# 180_schematic_3_layer.net
KiCad netlist of a schematic drawn in EAGLE
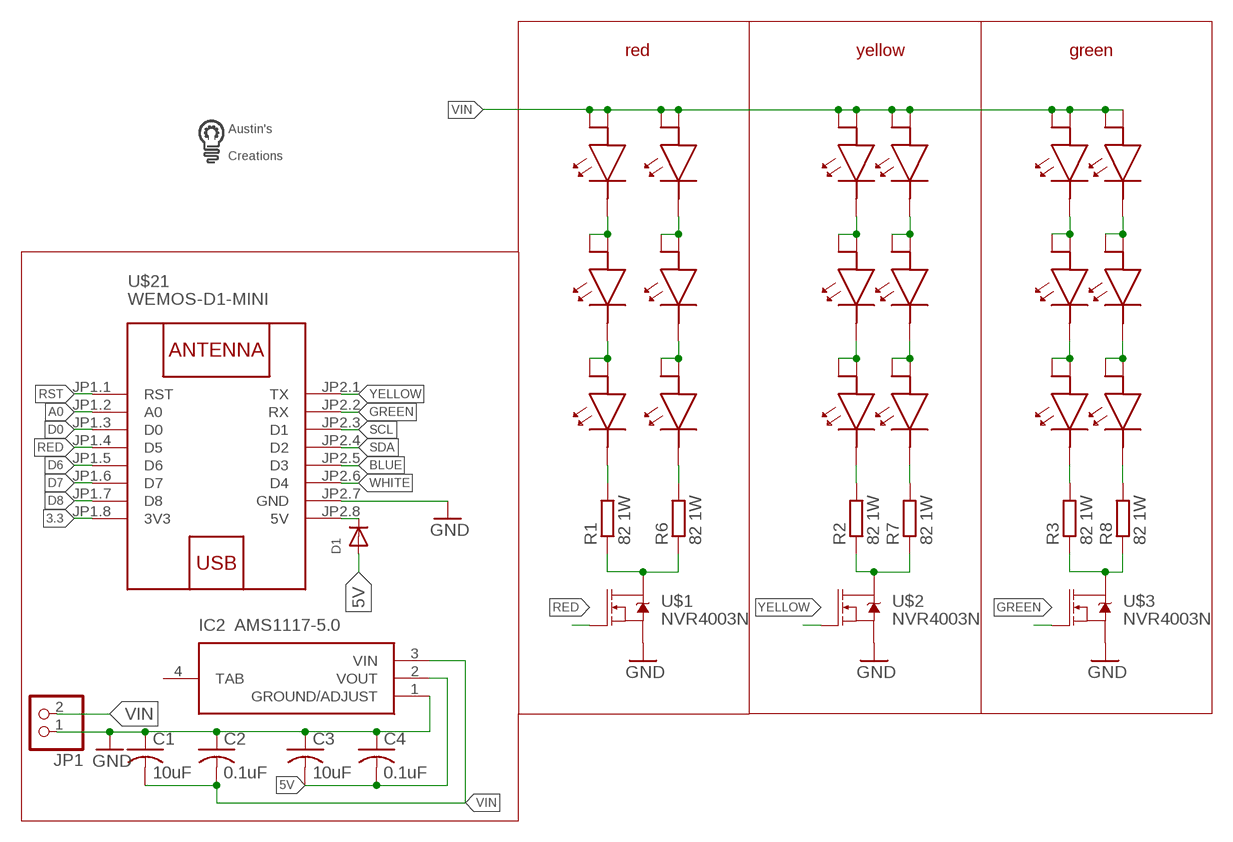
[diagram p0: schematic, sheet 1]

(export (version "E")
  (design (tool "Eeschema 10.0.6"))
  (components
    (comp (ref "C1")
      (value "10uF")
      (footprint "eagle-import:C0603")
      (libsource (lib "eagle-import") (part "C-USC0603"))
    )
    (comp (ref "C2")
      (value "0.1uF")
      (footprint "eagle-import:C0603")
      (libsource (lib "eagle-import") (part "C-USC0603"))
    )
    (comp (ref "C3")
      (value "10uF")
      (footprint "eagle-import:C0603")
      (libsource (lib "eagle-import") (part "C-USC0603"))
    )
    (comp (ref "C4")
      (value "0.1uF")
      (footprint "eagle-import:C0603")
      (libsource (lib "eagle-import") (part "C-USC0603"))
    )
    (comp (ref "D1")
      (value "DIODESOD-123")
      (footprint "eagle-import:SOD-123")
      (libsource (lib "eagle-import") (part "DIODESOD-123"))
    )
    (comp (ref "IC2")
      (value "AMS1117-5.0")
      (footprint "eagle-import:SOT229P700X180-4N")
      (libsource (lib "eagle-import") (part "AMS1117-5.0"))
    )
    (comp (ref "JP1")
      (value "PINHD-1X2")
      (footprint "eagle-import:1X02")
      (libsource (lib "eagle-import") (part "PINHD-1X2"))
    )
    (comp (ref "R1")
      (value "82 1W")
      (footprint "eagle-import:R2010")
      (libsource (lib "eagle-import") (part "R-EU_R2010"))
    )
    (comp (ref "R2")
      (value "82 1W")
      (footprint "eagle-import:R2010")
      (libsource (lib "eagle-import") (part "R-EU_R2010"))
    )
    (comp (ref "R3")
      (value "82 1W")
      (footprint "eagle-import:R2010")
      (libsource (lib "eagle-import") (part "R-EU_R2010"))
    )
    (comp (ref "R6")
      (value "82 1W")
      (footprint "eagle-import:R2010")
      (libsource (lib "eagle-import") (part "R-EU_R2010"))
    )
    (comp (ref "R7")
      (value "82 1W")
      (footprint "eagle-import:R2010")
      (libsource (lib "eagle-import") (part "R-EU_R2010"))
    )
    (comp (ref "R8")
      (value "82 1W")
      (footprint "eagle-import:R2010")
      (libsource (lib "eagle-import") (part "R-EU_R2010"))
    )
    (comp (ref "U$1")
      (value "NVR4003N")
      (footprint "eagle-import:SOT23")
      (libsource (lib "eagle-import") (part "NVR4003N"))
    )
    (comp (ref "U$2")
      (value "NVR4003N")
      (footprint "eagle-import:SOT23")
      (libsource (lib "eagle-import") (part "NVR4003N"))
    )
    (comp (ref "U$3")
      (value "NVR4003N")
      (footprint "eagle-import:SOT23")
      (libsource (lib "eagle-import") (part "NVR4003N"))
    )
    (comp (ref "U$6")
      (value "5730LED")
      (footprint "eagle-import:5730LED")
      (libsource (lib "eagle-import") (part "5730LED"))
    )
    (comp (ref "U$7")
      (value "5730LED")
      (footprint "eagle-import:5730LED")
      (libsource (lib "eagle-import") (part "5730LED"))
    )
    (comp (ref "U$8")
      (value "5730LED")
      (footprint "eagle-import:5730LED")
      (libsource (lib "eagle-import") (part "5730LED"))
    )
    (comp (ref "U$9")
      (value "5730LED")
      (footprint "eagle-import:5730LED")
      (libsource (lib "eagle-import") (part "5730LED"))
    )
    (comp (ref "U$10")
      (value "5730LED")
      (footprint "eagle-import:5730LED")
      (libsource (lib "eagle-import") (part "5730LED"))
    )
    (comp (ref "U$11")
      (value "5730LED")
      (footprint "eagle-import:5730LED")
      (libsource (lib "eagle-import") (part "5730LED"))
    )
    (comp (ref "U$12")
      (value "5730LED")
      (footprint "eagle-import:5730LED")
      (libsource (lib "eagle-import") (part "5730LED"))
    )
    (comp (ref "U$13")
      (value "5730LED")
      (footprint "eagle-import:5730LED")
      (libsource (lib "eagle-import") (part "5730LED"))
    )
    (comp (ref "U$14")
      (value "5730LED")
      (footprint "eagle-import:5730LED")
      (libsource (lib "eagle-import") (part "5730LED"))
    )
    (comp (ref "U$21")
      (value "WEMOS-D1-MINI")
      (footprint "eagle-import:WEMOS-D1-MINI")
      (libsource (lib "eagle-import") (part "WEMOS-D1-MINI"))
    )
    (comp (ref "U$22")
      (value "LOGO")
      (footprint "eagle-import:LOGO")
      (libsource (lib "eagle-import") (part "LOGO"))
    )
    (comp (ref "U$23")
      (value "5730LED")
      (footprint "eagle-import:5730LED")
      (libsource (lib "eagle-import") (part "5730LED"))
    )
    (comp (ref "U$24")
      (value "5730LED")
      (footprint "eagle-import:5730LED")
      (libsource (lib "eagle-import") (part "5730LED"))
    )
    (comp (ref "U$25")
      (value "5730LED")
      (footprint "eagle-import:5730LED")
      (libsource (lib "eagle-import") (part "5730LED"))
    )
    (comp (ref "U$26")
      (value "5730LED")
      (footprint "eagle-import:5730LED")
      (libsource (lib "eagle-import") (part "5730LED"))
    )
    (comp (ref "U$27")
      (value "5730LED")
      (footprint "eagle-import:5730LED")
      (libsource (lib "eagle-import") (part "5730LED"))
    )
    (comp (ref "U$28")
      (value "5730LED")
      (footprint "eagle-import:5730LED")
      (libsource (lib "eagle-import") (part "5730LED"))
    )
    (comp (ref "U$29")
      (value "5730LED")
      (footprint "eagle-import:5730LED")
      (libsource (lib "eagle-import") (part "5730LED"))
    )
    (comp (ref "U$30")
      (value "5730LED")
      (footprint "eagle-import:5730LED")
      (libsource (lib "eagle-import") (part "5730LED"))
    )
    (comp (ref "U$31")
      (value "5730LED")
      (footprint "eagle-import:5730LED")
      (libsource (lib "eagle-import") (part "5730LED"))
    )
  )
  (nets
    (net (code "1") (name "3.3") (class "Default")
      (node (ref "U$21") (pin "JP1.8") (pinfunction "3V3_JP1.8") (pintype "power_in"))
    )
    (net (code "2") (name "5V") (class "Default")
      (node (ref "C3") (pin "2") (pinfunction "2_2") (pintype "passive"))
      (node (ref "C4") (pin "2") (pinfunction "2_2") (pintype "passive"))
      (node (ref "D1") (pin "A") (pinfunction "A_A") (pintype "passive"))
      (node (ref "IC2") (pin "2") (pinfunction "VOUT_2") (pintype "bidirectional"))
    )
    (net (code "3") (name "A0") (class "Default")
      (node (ref "U$21") (pin "JP1.2") (pinfunction "A0_JP1.2") (pintype "bidirectional"))
    )
    (net (code "4") (name "BLUE") (class "Default")
      (node (ref "U$21") (pin "JP2.5") (pinfunction "D3_JP2.5") (pintype "bidirectional"))
    )
    (net (code "5") (name "D0") (class "Default")
      (node (ref "U$21") (pin "JP1.3") (pinfunction "D0_JP1.3") (pintype "bidirectional"))
    )
    (net (code "6") (name "D6") (class "Default")
      (node (ref "U$21") (pin "JP1.5") (pinfunction "D6_JP1.5") (pintype "bidirectional"))
    )
    (net (code "7") (name "D7") (class "Default")
      (node (ref "U$21") (pin "JP1.6") (pinfunction "D7_JP1.6") (pintype "bidirectional"))
    )
    (net (code "8") (name "D8") (class "Default")
      (node (ref "U$21") (pin "JP1.7") (pinfunction "D8_JP1.7") (pintype "bidirectional"))
    )
    (net (code "9") (name "GND") (class "Default")
      (node (ref "C1") (pin "1") (pinfunction "1_1") (pintype "passive"))
      (node (ref "C2") (pin "1") (pinfunction "1_1") (pintype "passive"))
      (node (ref "C3") (pin "1") (pinfunction "1_1") (pintype "passive"))
      (node (ref "C4") (pin "1") (pinfunction "1_1") (pintype "passive"))
      (node (ref "IC2") (pin "1") (pinfunction "GROUND/ADJUST_1") (pintype "bidirectional"))
      (node (ref "JP1") (pin "1") (pinfunction "1_1") (pintype "passive"))
      (node (ref "U$1") (pin "3") (pinfunction "S_3") (pintype "bidirectional"))
      (node (ref "U$2") (pin "3") (pinfunction "S_3") (pintype "bidirectional"))
      (node (ref "U$21") (pin "JP2.7") (pinfunction "GND_JP2.7") (pintype "power_in"))
      (node (ref "U$3") (pin "3") (pinfunction "S_3") (pintype "bidirectional"))
    )
    (net (code "10") (name "GREEN") (class "Default")
      (node (ref "U$21") (pin "JP2.2") (pinfunction "RX_JP2.2") (pintype "bidirectional"))
      (node (ref "U$3") (pin "2") (pinfunction "G_2") (pintype "bidirectional"))
    )
    (net (code "11") (name "Net-(R1-Pad2)") (class "Default")
      (node (ref "R1") (pin "2") (pinfunction "2_2") (pintype "passive"))
      (node (ref "U$8") (pin "P$2") (pinfunction "P$2_P$2") (pintype "bidirectional"))
    )
    (net (code "12") (name "Net-(R2-Pad2)") (class "Default")
      (node (ref "R2") (pin "2") (pinfunction "2_2") (pintype "passive"))
      (node (ref "U$11") (pin "P$2") (pinfunction "P$2_P$2") (pintype "bidirectional"))
    )
    (net (code "13") (name "Net-(R3-Pad2)") (class "Default")
      (node (ref "R3") (pin "2") (pinfunction "2_2") (pintype "passive"))
      (node (ref "U$14") (pin "P$2") (pinfunction "P$2_P$2") (pintype "bidirectional"))
    )
    (net (code "14") (name "Net-(R6-Pad2)") (class "Default")
      (node (ref "R6") (pin "2") (pinfunction "2_2") (pintype "passive"))
      (node (ref "U$25") (pin "P$2") (pinfunction "P$2_P$2") (pintype "bidirectional"))
    )
    (net (code "15") (name "Net-(R7-Pad2)") (class "Default")
      (node (ref "R7") (pin "2") (pinfunction "2_2") (pintype "passive"))
      (node (ref "U$28") (pin "P$2") (pinfunction "P$2_P$2") (pintype "bidirectional"))
    )
    (net (code "16") (name "Net-(R8-Pad2)") (class "Default")
      (node (ref "R8") (pin "2") (pinfunction "2_2") (pintype "passive"))
      (node (ref "U$31") (pin "P$2") (pinfunction "P$2_P$2") (pintype "bidirectional"))
    )
    (net (code "17") (name "Net-(U$1-D)") (class "Default")
      (node (ref "R1") (pin "1") (pinfunction "1_1") (pintype "passive"))
      (node (ref "R6") (pin "1") (pinfunction "1_1") (pintype "passive"))
      (node (ref "U$1") (pin "1") (pinfunction "D_1") (pintype "bidirectional"))
    )
    (net (code "18") (name "Net-(U$2-D)") (class "Default")
      (node (ref "R2") (pin "1") (pinfunction "1_1") (pintype "passive"))
      (node (ref "R7") (pin "1") (pinfunction "1_1") (pintype "passive"))
      (node (ref "U$2") (pin "1") (pinfunction "D_1") (pintype "bidirectional"))
    )
    (net (code "19") (name "Net-(U$3-D)") (class "Default")
      (node (ref "R3") (pin "1") (pinfunction "1_1") (pintype "passive"))
      (node (ref "R8") (pin "1") (pinfunction "1_1") (pintype "passive"))
      (node (ref "U$3") (pin "1") (pinfunction "D_1") (pintype "bidirectional"))
    )
    (net (code "20") (name "Net-(U$6-PadP$2)") (class "Default")
      (node (ref "U$6") (pin "P$2") (pinfunction "P$2_P$2") (pintype "bidirectional"))
      (node (ref "U$7") (pin "P$1") (pinfunction "P$1_P$1") (pintype "bidirectional"))
      (node (ref "U$7") (pin "P$3") (pinfunction "P$3_P$3") (pintype "bidirectional"))
    )
    (net (code "21") (name "Net-(U$7-PadP$2)") (class "Default")
      (node (ref "U$7") (pin "P$2") (pinfunction "P$2_P$2") (pintype "bidirectional"))
      (node (ref "U$8") (pin "P$1") (pinfunction "P$1_P$1") (pintype "bidirectional"))
      (node (ref "U$8") (pin "P$3") (pinfunction "P$3_P$3") (pintype "bidirectional"))
    )
    (net (code "22") (name "Net-(U$10-PadP$1)") (class "Default")
      (node (ref "U$10") (pin "P$1") (pinfunction "P$1_P$1") (pintype "bidirectional"))
      (node (ref "U$10") (pin "P$3") (pinfunction "P$3_P$3") (pintype "bidirectional"))
      (node (ref "U$9") (pin "P$2") (pinfunction "P$2_P$2") (pintype "bidirectional"))
    )
    (net (code "23") (name "Net-(U$10-PadP$2)") (class "Default")
      (node (ref "U$10") (pin "P$2") (pinfunction "P$2_P$2") (pintype "bidirectional"))
      (node (ref "U$11") (pin "P$1") (pinfunction "P$1_P$1") (pintype "bidirectional"))
      (node (ref "U$11") (pin "P$3") (pinfunction "P$3_P$3") (pintype "bidirectional"))
    )
    (net (code "24") (name "Net-(U$12-PadP$2)") (class "Default")
      (node (ref "U$12") (pin "P$2") (pinfunction "P$2_P$2") (pintype "bidirectional"))
      (node (ref "U$13") (pin "P$1") (pinfunction "P$1_P$1") (pintype "bidirectional"))
      (node (ref "U$13") (pin "P$3") (pinfunction "P$3_P$3") (pintype "bidirectional"))
    )
    (net (code "25") (name "Net-(U$13-PadP$2)") (class "Default")
      (node (ref "U$13") (pin "P$2") (pinfunction "P$2_P$2") (pintype "bidirectional"))
      (node (ref "U$14") (pin "P$1") (pinfunction "P$1_P$1") (pintype "bidirectional"))
      (node (ref "U$14") (pin "P$3") (pinfunction "P$3_P$3") (pintype "bidirectional"))
    )
    (net (code "26") (name "Net-(U$21-5V)") (class "Default")
      (node (ref "D1") (pin "C") (pinfunction "C_C") (pintype "passive"))
      (node (ref "U$21") (pin "JP2.8") (pinfunction "5V_JP2.8") (pintype "power_in"))
    )
    (net (code "27") (name "Net-(U$23-PadP$2)") (class "Default")
      (node (ref "U$23") (pin "P$2") (pinfunction "P$2_P$2") (pintype "bidirectional"))
      (node (ref "U$24") (pin "P$1") (pinfunction "P$1_P$1") (pintype "bidirectional"))
      (node (ref "U$24") (pin "P$3") (pinfunction "P$3_P$3") (pintype "bidirectional"))
    )
    (net (code "28") (name "Net-(U$24-PadP$2)") (class "Default")
      (node (ref "U$24") (pin "P$2") (pinfunction "P$2_P$2") (pintype "bidirectional"))
      (node (ref "U$25") (pin "P$1") (pinfunction "P$1_P$1") (pintype "bidirectional"))
      (node (ref "U$25") (pin "P$3") (pinfunction "P$3_P$3") (pintype "bidirectional"))
    )
    (net (code "29") (name "Net-(U$26-PadP$2)") (class "Default")
      (node (ref "U$26") (pin "P$2") (pinfunction "P$2_P$2") (pintype "bidirectional"))
      (node (ref "U$27") (pin "P$1") (pinfunction "P$1_P$1") (pintype "bidirectional"))
      (node (ref "U$27") (pin "P$3") (pinfunction "P$3_P$3") (pintype "bidirectional"))
    )
    (net (code "30") (name "Net-(U$27-PadP$2)") (class "Default")
      (node (ref "U$27") (pin "P$2") (pinfunction "P$2_P$2") (pintype "bidirectional"))
      (node (ref "U$28") (pin "P$1") (pinfunction "P$1_P$1") (pintype "bidirectional"))
      (node (ref "U$28") (pin "P$3") (pinfunction "P$3_P$3") (pintype "bidirectional"))
    )
    (net (code "31") (name "Net-(U$29-PadP$2)") (class "Default")
      (node (ref "U$29") (pin "P$2") (pinfunction "P$2_P$2") (pintype "bidirectional"))
      (node (ref "U$30") (pin "P$1") (pinfunction "P$1_P$1") (pintype "bidirectional"))
      (node (ref "U$30") (pin "P$3") (pinfunction "P$3_P$3") (pintype "bidirectional"))
    )
    (net (code "32") (name "Net-(U$30-PadP$2)") (class "Default")
      (node (ref "U$30") (pin "P$2") (pinfunction "P$2_P$2") (pintype "bidirectional"))
      (node (ref "U$31") (pin "P$1") (pinfunction "P$1_P$1") (pintype "bidirectional"))
      (node (ref "U$31") (pin "P$3") (pinfunction "P$3_P$3") (pintype "bidirectional"))
    )
    (net (code "33") (name "RED") (class "Default")
      (node (ref "U$1") (pin "2") (pinfunction "G_2") (pintype "bidirectional"))
      (node (ref "U$21") (pin "JP1.4") (pinfunction "D5_JP1.4") (pintype "bidirectional"))
    )
    (net (code "34") (name "RST") (class "Default")
      (node (ref "U$21") (pin "JP1.1") (pinfunction "RST_JP1.1") (pintype "bidirectional"))
    )
    (net (code "35") (name "SCL") (class "Default")
      (node (ref "U$21") (pin "JP2.3") (pinfunction "D1_JP2.3") (pintype "bidirectional"))
    )
    (net (code "36") (name "SDA") (class "Default")
      (node (ref "U$21") (pin "JP2.4") (pinfunction "D2_JP2.4") (pintype "bidirectional"))
    )
    (net (code "37") (name "VIN") (class "Default")
      (node (ref "C1") (pin "2") (pinfunction "2_2") (pintype "passive"))
      (node (ref "C2") (pin "2") (pinfunction "2_2") (pintype "passive"))
      (node (ref "IC2") (pin "3") (pinfunction "VIN_3") (pintype "bidirectional"))
      (node (ref "JP1") (pin "2") (pinfunction "2_2") (pintype "passive"))
      (node (ref "U$12") (pin "P$1") (pinfunction "P$1_P$1") (pintype "bidirectional"))
      (node (ref "U$12") (pin "P$3") (pinfunction "P$3_P$3") (pintype "bidirectional"))
      (node (ref "U$23") (pin "P$1") (pinfunction "P$1_P$1") (pintype "bidirectional"))
      (node (ref "U$23") (pin "P$3") (pinfunction "P$3_P$3") (pintype "bidirectional"))
      (node (ref "U$26") (pin "P$1") (pinfunction "P$1_P$1") (pintype "bidirectional"))
      (node (ref "U$26") (pin "P$3") (pinfunction "P$3_P$3") (pintype "bidirectional"))
      (node (ref "U$29") (pin "P$1") (pinfunction "P$1_P$1") (pintype "bidirectional"))
      (node (ref "U$29") (pin "P$3") (pinfunction "P$3_P$3") (pintype "bidirectional"))
      (node (ref "U$6") (pin "P$1") (pinfunction "P$1_P$1") (pintype "bidirectional"))
      (node (ref "U$6") (pin "P$3") (pinfunction "P$3_P$3") (pintype "bidirectional"))
      (node (ref "U$9") (pin "P$1") (pinfunction "P$1_P$1") (pintype "bidirectional"))
      (node (ref "U$9") (pin "P$3") (pinfunction "P$3_P$3") (pintype "bidirectional"))
    )
    (net (code "38") (name "WHITE") (class "Default")
      (node (ref "U$21") (pin "JP2.6") (pinfunction "D4_JP2.6") (pintype "bidirectional"))
    )
    (net (code "39") (name "YELLOW") (class "Default")
      (node (ref "U$2") (pin "2") (pinfunction "G_2") (pintype "bidirectional"))
      (node (ref "U$21") (pin "JP2.1") (pinfunction "TX_JP2.1") (pintype "bidirectional"))
    )
    (net (code "40") (name "unconnected-(IC2-TAB-Pad4)") (class "Default")
      (node (ref "IC2") (pin "4") (pinfunction "TAB_4") (pintype "bidirectional"))
    )
  )
)
